# legdrive.net
KiCad netlist of a schematic drawn in Altium Designer
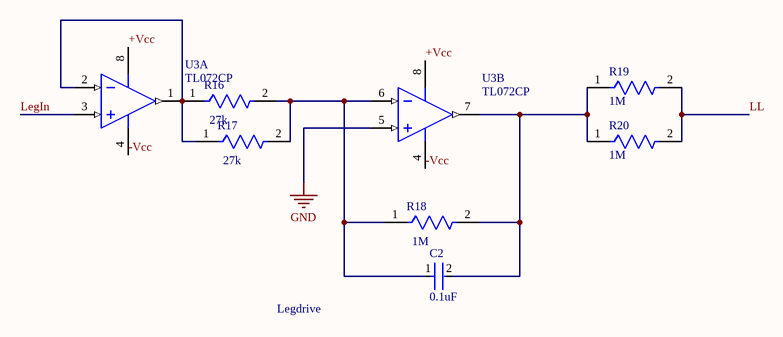
[diagram p0: legdrive.SchDoc]

(export (version "E")
  (design (tool "Eeschema 10.0.6"))
  (components
    (comp (ref "C2")
      (value "0.1uF")
      (footprint "FP-K15H5-MFG")
      (description "CAP CER 0.1UF 50V X7R RADIAL")
      (fields (field (name "VOLTAGE") "50V") (field (name "TOLERANCE") "10%"))
      (libsource (lib "Altium Content Vault") (part "11868f565c42a9108669ba33697ecf6"))
    )
    (comp (ref "R16")
      (value "27k")
      (footprint "FP-CFR-25-MFG")
      (description "RES 10 OHM 1/4W 5% AXIAL")
      (fields (field (name "TOLERANCE") "5%"))
      (libsource (lib "Altium Content Vault") (part "1029c3af85768c4190bb7ad29bc67b5"))
    )
    (comp (ref "R17")
      (value "27k")
      (footprint "FP-CFR-25-MFG")
      (description "RES 10 OHM 1/4W 5% AXIAL")
      (fields (field (name "TOLERANCE") "5%"))
      (libsource (lib "Altium Content Vault") (part "1029c3af85768c4190bb7ad29bc67b5"))
    )
    (comp (ref "R18")
      (value "1M")
      (footprint "FP-CFR-25-MFG")
      (description "RES 10 OHM 1/4W 5% AXIAL")
      (fields (field (name "TOLERANCE") "5%"))
      (libsource (lib "Altium Content Vault") (part "1029c3af85768c4190bb7ad29bc67b5"))
    )
    (comp (ref "R19")
      (value "1M")
      (footprint "FP-CFR-25-MFG")
      (description "RES 10 OHM 1/4W 5% AXIAL")
      (fields (field (name "TOLERANCE") "5%"))
      (libsource (lib "Altium Content Vault") (part "1029c3af85768c4190bb7ad29bc67b5"))
    )
    (comp (ref "R20")
      (value "1M")
      (footprint "FP-CFR-25-MFG")
      (description "RES 10 OHM 1/4W 5% AXIAL")
      (fields (field (name "TOLERANCE") "5%"))
      (libsource (lib "Altium Content Vault") (part "1029c3af85768c4190bb7ad29bc67b5"))
    )
    (comp (ref "U3")
      (value "TL072CP")
      (footprint "P0008A")
      (fields (field (name "MANUFACTURER") "Texas Instruments"))
      (libsource (lib "Altium Content Vault") (part "TI-AMP-D6-2-8_D"))
    )
  )
  (nets
    (net (code "1") (name "/+Vcc") (class "Default")
      (node (ref "U3") (pin "8") (pinfunction "VCC+_8") (pintype "power_in"))
    )
    (net (code "2") (name "/-Vcc") (class "Default")
      (node (ref "U3") (pin "4") (pinfunction "VCC-_4") (pintype "power_in"))
    )
    (net (code "3") (name "/LL") (class "Default")
      (node (ref "R19") (pin "2") (pinfunction "2_2") (pintype "passive"))
      (node (ref "R20") (pin "2") (pinfunction "2_2") (pintype "passive"))
    )
    (net (code "4") (name "/LegIn") (class "Default")
      (node (ref "U3") (pin "3") (pinfunction "IN1+_3") (pintype "input"))
    )
    (net (code "5") (name "GND") (class "Default")
      (node (ref "U3") (pin "5") (pinfunction "IN2+_5") (pintype "input"))
    )
    (net (code "6") (name "Net-(U3A-IN1-)") (class "Default")
      (node (ref "R16") (pin "1") (pinfunction "1_1") (pintype "passive"))
      (node (ref "R17") (pin "1") (pinfunction "1_1") (pintype "passive"))
      (node (ref "U3") (pin "1") (pinfunction "OUT1_1") (pintype "output"))
      (node (ref "U3") (pin "2") (pinfunction "IN1-_2") (pintype "input"))
    )
    (net (code "7") (name "Net-(U3B-IN2-)") (class "Default")
      (node (ref "C2") (pin "1") (pinfunction "1_1") (pintype "passive"))
      (node (ref "R16") (pin "2") (pinfunction "2_2") (pintype "passive"))
      (node (ref "R17") (pin "2") (pinfunction "2_2") (pintype "passive"))
      (node (ref "R18") (pin "1") (pinfunction "1_1") (pintype "passive"))
      (node (ref "U3") (pin "6") (pinfunction "IN2-_6") (pintype "input"))
    )
    (net (code "8") (name "Net-(U3B-OUT2)") (class "Default")
      (node (ref "C2") (pin "2") (pinfunction "2_2") (pintype "passive"))
      (node (ref "R18") (pin "2") (pinfunction "2_2") (pintype "passive"))
      (node (ref "R19") (pin "1") (pinfunction "1_1") (pintype "passive"))
      (node (ref "R20") (pin "1") (pinfunction "1_1") (pintype "passive"))
      (node (ref "U3") (pin "7") (pinfunction "OUT2_7") (pintype "output"))
    )
  )
)
